# schematic.net
KiCad netlist of a schematic drawn in EasyEDA
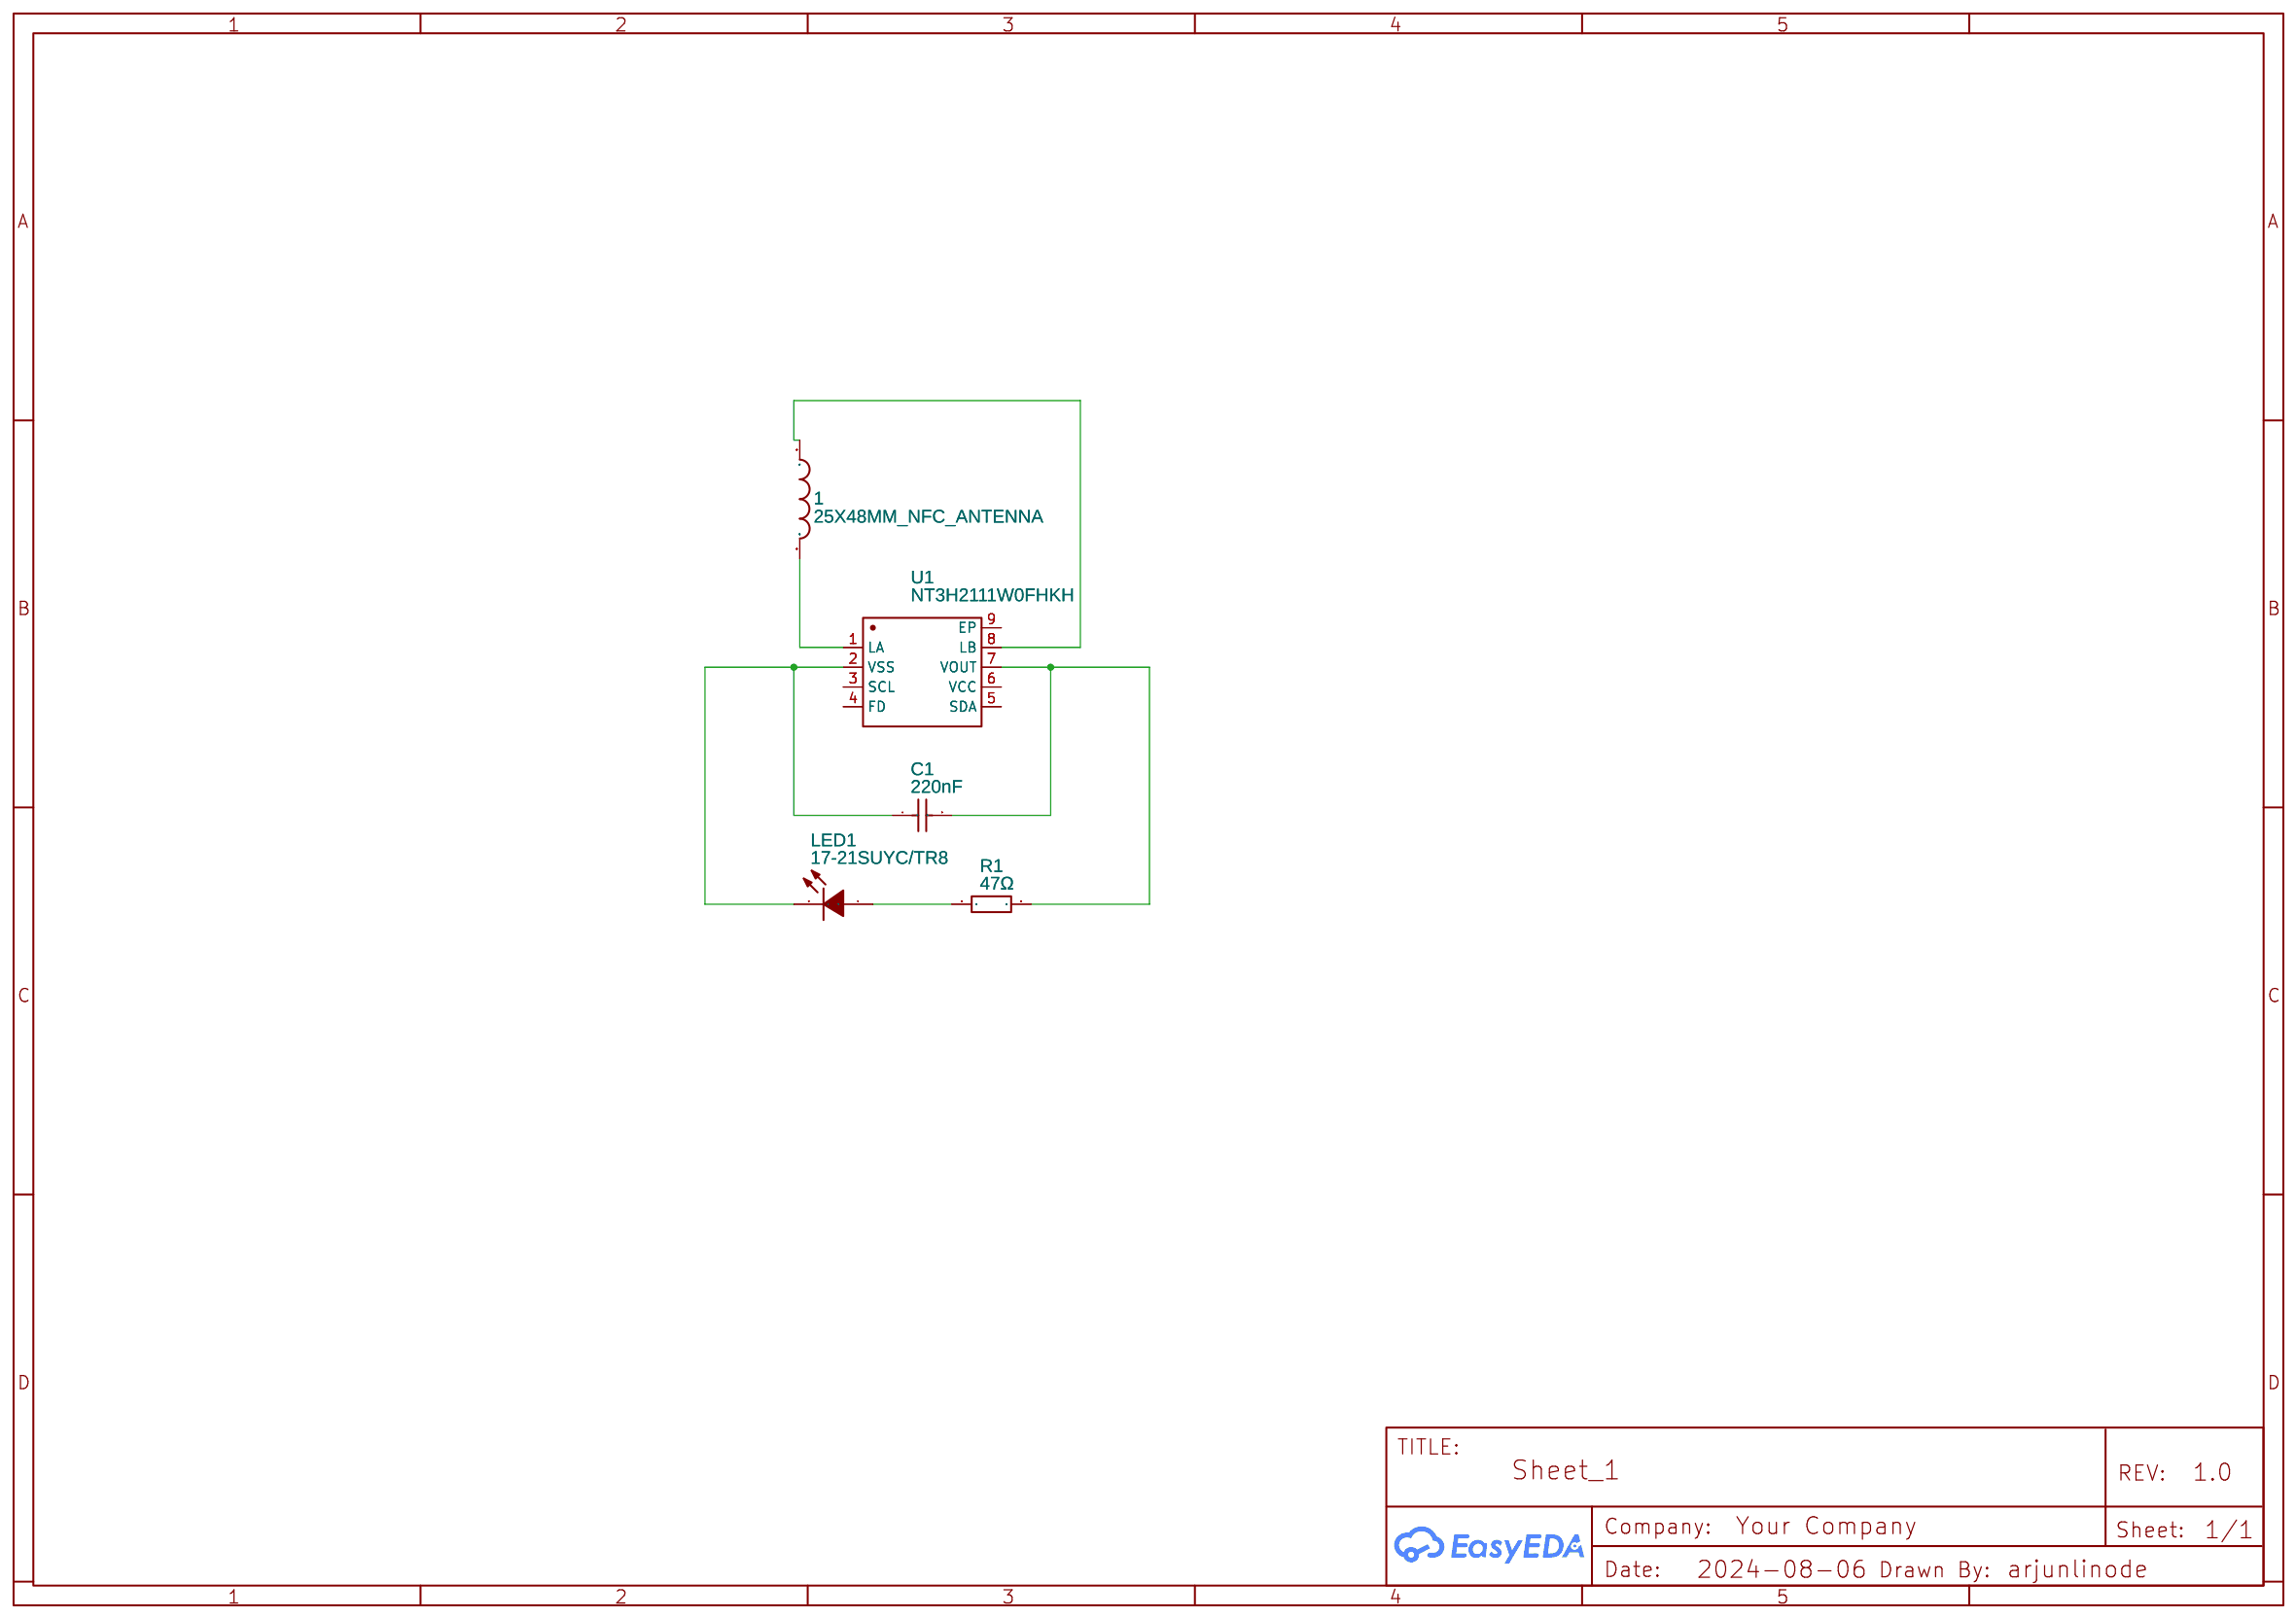
[diagram p0: schematic sheet]

(export (version "E")
  (design (tool "Eeschema 10.0.6"))
  (components
    (comp (ref "1") (value "25X48MM_NFC_ANTENNA") (libsource (lib "") (part "25X48MM_NFC_ANTENNA")))
    (comp (ref "C1")
      (value "220nF")
      (fields
        (field (name "Manufacturer Part") "CL10B224KA8NNNC")
        (field (name "Manufacturer") "SAMSUNG(三星)")
      )
      (libsource (lib "") (part "CL10B224KA8NNNC"))
    )
    (comp (ref "LED1")
      (value "17-21SUYC/TR8")
      (fields (field (name "Manufacturer Part") "KT-0805黄灯") (field (name "Manufacturer") "KENTO"))
      (libsource (lib "") (part "17-21SUYC/TR8"))
    )
    (comp (ref "R1")
      (value "47Ω")
      (fields
        (field (name "Manufacturer Part") "0603WAF470JT5E")
        (field (name "Manufacturer") "UNI-ROYAL(厚声)")
      )
      (libsource (lib "") (part "0603WAF470JT5E"))
    )
    (comp (ref "U1")
      (value "NT3H2111W0FHKH")
      (fields (field (name "Manufacturer") "NXP(恩智浦)"))
      (libsource (lib "") (part "NT3H2111W0FHKH"))
    )
  )
  (nets
    (net (code "1") (name "Net-(LED1-+)") (class "Default")
      (node (ref "LED1") (pin "1") (pinfunction "+_1") (pintype "unspecified"))
      (node (ref "R1") (pin "1") (pinfunction "1_1") (pintype "input"))
    )
    (net (code "2") (name "Net-(LED1--)") (class "Default")
      (node (ref "C1") (pin "1") (pinfunction "1_1") (pintype "input"))
      (node (ref "LED1") (pin "2") (pinfunction "-_2") (pintype "unspecified"))
      (node (ref "U1") (pin "2") (pinfunction "VSS_2") (pintype "unspecified"))
    )
    (net (code "3") (name "Net-(U1-LA)") (class "Default")
      (node (ref "1") (pin "P$2") (pinfunction "P$2_P$2") (pintype "bidirectional"))
      (node (ref "U1") (pin "1") (pinfunction "LA_1") (pintype "unspecified"))
    )
    (net (code "4") (name "Net-(U1-LB)") (class "Default")
      (node (ref "1") (pin "P$1") (pinfunction "P$1_P$1") (pintype "bidirectional"))
      (node (ref "U1") (pin "8") (pinfunction "LB_8") (pintype "unspecified"))
    )
    (net (code "5") (name "Net-(U1-VOUT)") (class "Default")
      (node (ref "C1") (pin "2") (pinfunction "2_2") (pintype "input"))
      (node (ref "R1") (pin "2") (pinfunction "2_2") (pintype "input"))
      (node (ref "U1") (pin "7") (pinfunction "VOUT_7") (pintype "unspecified"))
    )
    (net (code "6") (name "unconnected-(U1-EP-Pad9)") (class "Default")
      (node (ref "U1") (pin "9") (pinfunction "EP_9") (pintype "unspecified"))
    )
    (net (code "7") (name "unconnected-(U1-FD-Pad4)") (class "Default")
      (node (ref "U1") (pin "4") (pinfunction "FD_4") (pintype "unspecified"))
    )
    (net (code "8") (name "unconnected-(U1-SCL-Pad3)") (class "Default")
      (node (ref "U1") (pin "3") (pinfunction "SCL_3") (pintype "unspecified"))
    )
    (net (code "9") (name "unconnected-(U1-SDA-Pad5)") (class "Default")
      (node (ref "U1") (pin "5") (pinfunction "SDA_5") (pintype "unspecified"))
    )
    (net (code "10") (name "unconnected-(U1-VCC-Pad6)") (class "Default")
      (node (ref "U1") (pin "6") (pinfunction "VCC_6") (pintype "unspecified"))
    )
  )
)
